# Schematic.net
KiCad netlist of a schematic drawn in Altium Designer
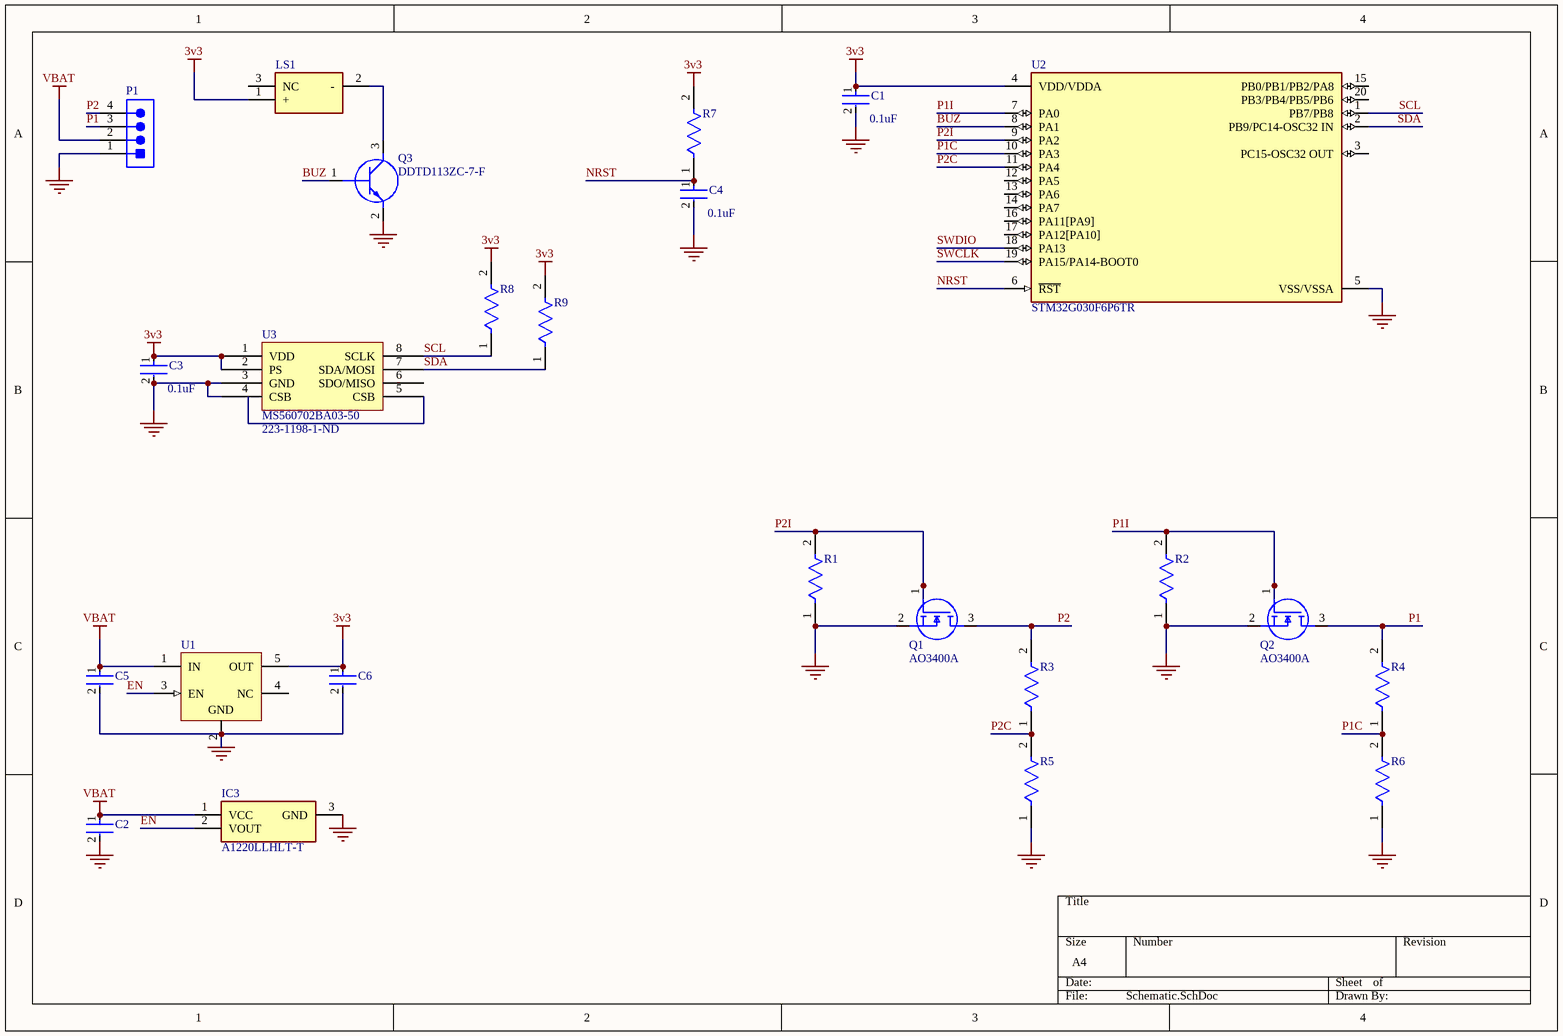
[diagram p0: Schematic.SchDoc]

(export (version "E")
  (design (tool "Eeschema 10.0.6"))
  (components
    (comp (ref "C1")
      (value "0.1uF")
      (footprint "FP-C0402-BB-MFG")
      (description "CAP CER 0.1UF 10V X5R 0402")
      (fields (field (name "MANUFACTURER") "Kemet") (field (name "TOLERANCE") "0.1"))
      (libsource (lib "Altium Content Vault") (part "b4654b650e69147ec39a6b967a45e02"))
    )
    (comp (ref "C2")
      (value "C0402C105K8PACTU")
      (footprint "FP-C0402C105K8PACTU-MFG")
      (description "CAP CER 1UF 10V X5R 0402")
      (fields (field (name "VOLTAGE") "10V") (field (name "TOLERANCE") "10%"))
      (libsource (lib "Altium Content Vault") (part "11868f565c42a9108669ba33697ecf6"))
    )
    (comp (ref "C3")
      (value "0.1uF")
      (footprint "FP-C0402-BB-MFG")
      (description "CAP CER 0.1UF 10V X5R 0402")
      (fields (field (name "MANUFACTURER") "Kemet") (field (name "TOLERANCE") "0.1"))
      (libsource (lib "Altium Content Vault") (part "b4654b650e69147ec39a6b967a45e02"))
    )
    (comp (ref "C4")
      (value "0.1uF")
      (footprint "FP-C0402-BB-MFG")
      (description "CAP CER 0.1UF 10V X5R 0402")
      (fields (field (name "MANUFACTURER") "Kemet") (field (name "TOLERANCE") "0.1"))
      (libsource (lib "Altium Content Vault") (part "b4654b650e69147ec39a6b967a45e02"))
    )
    (comp (ref "C5")
      (value "C0402C105K8PACTU")
      (footprint "FP-C0402C105K8PACTU-MFG")
      (description "CAP CER 1UF 10V X5R 0402")
      (fields (field (name "VOLTAGE") "10V") (field (name "TOLERANCE") "10%"))
      (libsource (lib "Altium Content Vault") (part "11868f565c42a9108669ba33697ecf6"))
    )
    (comp (ref "C6")
      (value "C0402C105K8PACTU")
      (footprint "FP-C0402C105K8PACTU-MFG")
      (description "CAP CER 1UF 10V X5R 0402")
      (fields (field (name "VOLTAGE") "10V") (field (name "TOLERANCE") "10%"))
      (libsource (lib "Altium Content Vault") (part "11868f565c42a9108669ba33697ecf6"))
    )
    (comp (ref "IC3")
      (value "A1220LLHLT-T")
      (footprint "SamacSys:A3213ELHLTT")
      (description "Integrated Circuit")
      (libsource (lib "*") (part "A1220LLHLT-T"))
    )
    (comp (ref "LS1")
      (value "CMT-0525-75-SMT-TR")
      (footprint "SamacSys:CMT052575SMTTR")
      (description "Loudspeaker or Buzzer")
      (libsource (lib "*") (part "CMT-0525-75-SMT-TR"))
    )
    (comp (ref "P1")
      (value "GRPB041VWVN-RC")
      (footprint "SLIN-GRPB041VWVN-RC_V")
      (fields (field (name "MANUFACTURER") "Sullins"))
      (libsource (lib "Altium Content Vault") (part "CN-1P-M-R4"))
    )
    (comp (ref "Q1")
      (value "AO3400A")
      (footprint "SamacSys:SOT95P280X125-3N")
      (description "MOSFET (N-Channel)")
      (libsource (lib "*") (part "AO3400A"))
    )
    (comp (ref "Q2")
      (value "AO3400A")
      (footprint "SamacSys:SOT95P280X125-3N")
      (description "MOSFET (N-Channel)")
      (libsource (lib "*") (part "AO3400A"))
    )
    (comp (ref "Q3")
      (value "DDTD113ZC-7-F")
      (footprint "SamacSys:SOT96P240X110-3N")
      (description "Transistor BJT NPN")
      (libsource (lib "*") (part "DDTD113ZC-7-F"))
    )
    (comp (ref "R1")
      (value "CRCW0402100KFKED")
      (footprint "FP-CRCW0402-e3-IPC_C")
      (description "RES Thick Film, 100kΩ, 1%, 0.063W, 100ppm/°C, 0402")
      (fields (field (name "TOLERANCE") "1%"))
      (libsource (lib "Altium Content Vault") (part "1029c3af85768c4190bb7ad29bc67b5"))
    )
    (comp (ref "R2")
      (value "CRCW0402100KFKED")
      (footprint "FP-CRCW0402-e3-IPC_C")
      (description "RES Thick Film, 100kΩ, 1%, 0.063W, 100ppm/°C, 0402")
      (fields (field (name "TOLERANCE") "1%"))
      (libsource (lib "Altium Content Vault") (part "1029c3af85768c4190bb7ad29bc67b5"))
    )
    (comp (ref "R3")
      (value "CRCW0402100KFKED")
      (footprint "FP-CRCW0402-e3-IPC_C")
      (description "RES Thick Film, 100kΩ, 1%, 0.063W, 100ppm/°C, 0402")
      (fields (field (name "TOLERANCE") "1%"))
      (libsource (lib "Altium Content Vault") (part "1029c3af85768c4190bb7ad29bc67b5"))
    )
    (comp (ref "R4")
      (value "CRCW0402100KFKED")
      (footprint "FP-CRCW0402-e3-IPC_C")
      (description "RES Thick Film, 100kΩ, 1%, 0.063W, 100ppm/°C, 0402")
      (fields (field (name "TOLERANCE") "1%"))
      (libsource (lib "Altium Content Vault") (part "1029c3af85768c4190bb7ad29bc67b5"))
    )
    (comp (ref "R5")
      (value "CRCW040250K0FKED")
      (footprint "FP-CRCW0402-e3-IPC_A")
      (description "RES Thick Film, 50kΩ, 1%, 0.063W, 100ppm/°C, 0402")
      (fields (field (name "TOLERANCE") "1%"))
      (libsource (lib "Altium Content Vault") (part "1029c3af85768c4190bb7ad29bc67b5"))
    )
    (comp (ref "R6")
      (value "CRCW040250K0FKED")
      (footprint "FP-CRCW0402-e3-IPC_A")
      (description "RES Thick Film, 50kΩ, 1%, 0.063W, 100ppm/°C, 0402")
      (fields (field (name "TOLERANCE") "1%"))
      (libsource (lib "Altium Content Vault") (part "1029c3af85768c4190bb7ad29bc67b5"))
    )
    (comp (ref "R7")
      (value "CRCW040250K0FKED")
      (footprint "FP-CRCW0402-e3-IPC_A")
      (description "RES Thick Film, 50kΩ, 1%, 0.063W, 100ppm/°C, 0402")
      (fields (field (name "TOLERANCE") "1%"))
      (libsource (lib "Altium Content Vault") (part "1029c3af85768c4190bb7ad29bc67b5"))
    )
    (comp (ref "R8")
      (value "RC0402JR-074K7L")
      (footprint "FP-RC0402-0_4-MFG")
      (fields (field (name "TOLERANCE") "5%"))
      (libsource (lib "Altium Content Vault") (part "RC0402JR-074K7L"))
    )
    (comp (ref "R9")
      (value "RC0402JR-074K7L")
      (footprint "FP-RC0402-0_4-MFG")
      (fields (field (name "TOLERANCE") "5%"))
      (libsource (lib "Altium Content Vault") (part "RC0402JR-074K7L"))
    )
    (comp (ref "U1")
      (value "TLV70033DCKR")
      (footprint "DCK0005A_M")
      (fields (field (name "MANUFACTURER") "Texas Instruments"))
      (libsource (lib "Altium Content Vault") (part "TI-TXX7XXXX-5"))
    )
    (comp (ref "U2")
      (value "STM32G030F6P6TR")
      (footprint "FP-TSSOP20-YA-IPC_A")
      (description "IC MCU 32BIT 32KB FLASH 20TSSOP")
      (libsource (lib "Altium Content Vault") (part "be9f3bd3d72e89be6370f9e56c175d8"))
    )
    (comp (ref "U3")
      (value "MS560702BA03-50")
      (footprint "MS5607")
      (description "Barometric Pressure Sensor I2C/SPI")
      (fields
        (field (name "SUPPLIER PART NUMBER 1") "223-1198-1-ND")
        (field (name "MADE BY") "*")
        (field (name "REVIEWED BY") "Adam Rising")
      )
      (libsource (lib "USCRPL") (part "MS560702BA03-50"))
    )
  )
  (nets
    (net (code "1") (name "/BUZ") (class "Default")
      (node (ref "Q3") (pin "1") (pinfunction "B_1") (pintype "passive"))
      (node (ref "U2") (pin "8") (pinfunction "PA1_8") (pintype "bidirectional"))
    )
    (net (code "2") (name "/EN") (class "Default")
      (node (ref "IC3") (pin "2") (pinfunction "VOUT_2") (pintype "passive"))
      (node (ref "U1") (pin "3") (pinfunction "EN_3") (pintype "input"))
    )
    (net (code "3") (name "/NRST") (class "Default")
      (node (ref "C4") (pin "1") (pinfunction "1_1") (pintype "passive"))
      (node (ref "R7") (pin "1") (pinfunction "1_1") (pintype "passive"))
      (node (ref "U2") (pin "6") (pinfunction "~{RST}_6") (pintype "input"))
    )
    (net (code "4") (name "/P1") (class "Default")
      (node (ref "P1") (pin "3") (pinfunction "3_3") (pintype "passive"))
      (node (ref "Q2") (pin "3") (pinfunction "D_3") (pintype "passive"))
      (node (ref "R4") (pin "2") (pinfunction "2_2") (pintype "passive"))
    )
    (net (code "5") (name "/P1C") (class "Default")
      (node (ref "R4") (pin "1") (pinfunction "1_1") (pintype "passive"))
      (node (ref "R6") (pin "2") (pinfunction "2_2") (pintype "passive"))
      (node (ref "U2") (pin "10") (pinfunction "PA3_10") (pintype "bidirectional"))
    )
    (net (code "6") (name "/P1I") (class "Default")
      (node (ref "Q2") (pin "1") (pinfunction "G_1") (pintype "passive"))
      (node (ref "R2") (pin "2") (pinfunction "2_2") (pintype "passive"))
      (node (ref "U2") (pin "7") (pinfunction "PA0_7") (pintype "bidirectional"))
    )
    (net (code "7") (name "/P2") (class "Default")
      (node (ref "P1") (pin "4") (pinfunction "4_4") (pintype "passive"))
      (node (ref "Q1") (pin "3") (pinfunction "D_3") (pintype "passive"))
      (node (ref "R3") (pin "2") (pinfunction "2_2") (pintype "passive"))
    )
    (net (code "8") (name "/P2C") (class "Default")
      (node (ref "R3") (pin "1") (pinfunction "1_1") (pintype "passive"))
      (node (ref "R5") (pin "2") (pinfunction "2_2") (pintype "passive"))
      (node (ref "U2") (pin "11") (pinfunction "PA4_11") (pintype "bidirectional"))
    )
    (net (code "9") (name "/P2I") (class "Default")
      (node (ref "Q1") (pin "1") (pinfunction "G_1") (pintype "passive"))
      (node (ref "R1") (pin "2") (pinfunction "2_2") (pintype "passive"))
      (node (ref "U2") (pin "9") (pinfunction "PA2_9") (pintype "bidirectional"))
    )
    (net (code "10") (name "/SCL") (class "Default")
      (node (ref "R8") (pin "1") (pinfunction "1_1") (pintype "passive"))
      (node (ref "U2") (pin "1") (pinfunction "PB7/PB8_1") (pintype "bidirectional"))
      (node (ref "U3") (pin "8") (pinfunction "SCLK_8") (pintype "passive"))
    )
    (net (code "11") (name "/SDA") (class "Default")
      (node (ref "R9") (pin "1") (pinfunction "1_1") (pintype "passive"))
      (node (ref "U2") (pin "2") (pinfunction "PB9/PC14-OSC32_IN_2") (pintype "bidirectional"))
      (node (ref "U3") (pin "7") (pinfunction "SDA/MOSI_7") (pintype "passive"))
    )
    (net (code "12") (name "/SWCLK") (class "Default")
      (node (ref "U2") (pin "19") (pinfunction "PA15/PA14-BOOT0_19") (pintype "bidirectional"))
    )
    (net (code "13") (name "/SWDIO") (class "Default")
      (node (ref "U2") (pin "18") (pinfunction "PA13_18") (pintype "bidirectional"))
    )
    (net (code "14") (name "3v3") (class "Default")
      (node (ref "C1") (pin "1") (pinfunction "1_1") (pintype "passive"))
      (node (ref "C3") (pin "1") (pinfunction "1_1") (pintype "passive"))
      (node (ref "C6") (pin "1") (pinfunction "1_1") (pintype "passive"))
      (node (ref "LS1") (pin "1") (pinfunction "+_1") (pintype "passive"))
      (node (ref "R7") (pin "2") (pinfunction "2_2") (pintype "passive"))
      (node (ref "R8") (pin "2") (pinfunction "2_2") (pintype "passive"))
      (node (ref "R9") (pin "2") (pinfunction "2_2") (pintype "passive"))
      (node (ref "U1") (pin "5") (pinfunction "OUT_5") (pintype "power_in"))
      (node (ref "U2") (pin "4") (pinfunction "VDD/VDDA_4") (pintype "power_in"))
      (node (ref "U3") (pin "1") (pinfunction "VDD_1") (pintype "passive"))
      (node (ref "U3") (pin "2") (pinfunction "PS_2") (pintype "passive"))
    )
    (net (code "15") (name "GND") (class "Default")
      (node (ref "C1") (pin "2") (pinfunction "2_2") (pintype "passive"))
      (node (ref "C2") (pin "2") (pinfunction "2_2") (pintype "passive"))
      (node (ref "C3") (pin "2") (pinfunction "2_2") (pintype "passive"))
      (node (ref "C4") (pin "2") (pinfunction "2_2") (pintype "passive"))
      (node (ref "C5") (pin "2") (pinfunction "2_2") (pintype "passive"))
      (node (ref "C6") (pin "2") (pinfunction "2_2") (pintype "passive"))
      (node (ref "IC3") (pin "3") (pinfunction "GND_3") (pintype "passive"))
      (node (ref "P1") (pin "1") (pinfunction "1_1") (pintype "passive"))
      (node (ref "Q1") (pin "2") (pinfunction "S_2") (pintype "passive"))
      (node (ref "Q2") (pin "2") (pinfunction "S_2") (pintype "passive"))
      (node (ref "Q3") (pin "2") (pinfunction "E_2") (pintype "passive"))
      (node (ref "R1") (pin "1") (pinfunction "1_1") (pintype "passive"))
      (node (ref "R2") (pin "1") (pinfunction "1_1") (pintype "passive"))
      (node (ref "R5") (pin "1") (pinfunction "1_1") (pintype "passive"))
      (node (ref "R6") (pin "1") (pinfunction "1_1") (pintype "passive"))
      (node (ref "U1") (pin "2") (pinfunction "GND_2") (pintype "power_in"))
      (node (ref "U2") (pin "5") (pinfunction "VSS/VSSA_5") (pintype "power_in"))
      (node (ref "U3") (pin "3") (pinfunction "GND_3") (pintype "passive"))
      (node (ref "U3") (pin "4") (pinfunction "CSB_4") (pintype "passive"))
    )
    (net (code "16") (name "Net-(LS1--)") (class "Default")
      (node (ref "LS1") (pin "2") (pinfunction "-_2") (pintype "passive"))
      (node (ref "Q3") (pin "3") (pinfunction "C_3") (pintype "passive"))
    )
    (net (code "17") (name "VBAT") (class "Default")
      (node (ref "C2") (pin "1") (pinfunction "1_1") (pintype "passive"))
      (node (ref "C5") (pin "1") (pinfunction "1_1") (pintype "passive"))
      (node (ref "IC3") (pin "1") (pinfunction "VCC_1") (pintype "passive"))
      (node (ref "P1") (pin "2") (pinfunction "2_2") (pintype "passive"))
      (node (ref "U1") (pin "1") (pinfunction "IN_1") (pintype "power_in"))
    )
    (net (code "18") (name "unconnected-(LS1-NC-Pad3)") (class "Default")
      (node (ref "LS1") (pin "3") (pinfunction "NC_3") (pintype "passive"))
    )
    (net (code "19") (name "unconnected-(U1-NC-Pad4)") (class "Default")
      (node (ref "U1") (pin "4") (pinfunction "NC_4") (pintype "passive"))
    )
    (net (code "20") (name "unconnected-(U2-PA5-Pad12)") (class "Default")
      (node (ref "U2") (pin "12") (pinfunction "PA5_12") (pintype "bidirectional"))
    )
    (net (code "21") (name "unconnected-(U2-PA6-Pad13)") (class "Default")
      (node (ref "U2") (pin "13") (pinfunction "PA6_13") (pintype "bidirectional"))
    )
    (net (code "22") (name "unconnected-(U2-PA7-Pad14)") (class "Default")
      (node (ref "U2") (pin "14") (pinfunction "PA7_14") (pintype "bidirectional"))
    )
    (net (code "23") (name "unconnected-(U2-PA11[PA9]-Pad16)") (class "Default")
      (node (ref "U2") (pin "16") (pinfunction "PA11[PA9]_16") (pintype "bidirectional"))
    )
    (net (code "24") (name "unconnected-(U2-PA12[PA10]-Pad17)") (class "Default")
      (node (ref "U2") (pin "17") (pinfunction "PA12[PA10]_17") (pintype "bidirectional"))
    )
    (net (code "25") (name "unconnected-(U2-PB0{slash}PB1{slash}PB2{slash}PA8-Pad15)") (class "Default")
      (node (ref "U2") (pin "15") (pinfunction "PB0/PB1/PB2/PA8_15") (pintype "bidirectional"))
    )
    (net (code "26") (name "unconnected-(U2-PB3{slash}PB4{slash}PB5{slash}PB6-Pad20)") (class "Default")
      (node (ref "U2") (pin "20") (pinfunction "PB3/PB4/PB5/PB6_20") (pintype "bidirectional"))
    )
    (net (code "27") (name "unconnected-(U2-PC15-OSC32_OUT-Pad3)") (class "Default")
      (node (ref "U2") (pin "3") (pinfunction "PC15-OSC32_OUT_3") (pintype "bidirectional"))
    )
    (net (code "28") (name "unconnected-(U3-CSB-Pad5)") (class "Default")
      (node (ref "U3") (pin "5") (pinfunction "CSB_5") (pintype "passive"))
    )
    (net (code "29") (name "unconnected-(U3-SDO{slash}MISO-Pad6)") (class "Default")
      (node (ref "U3") (pin "6") (pinfunction "SDO/MISO_6") (pintype "passive"))
    )
  )
)
